# KeyBoard.net
KiCad netlist of a schematic drawn in Altium Designer
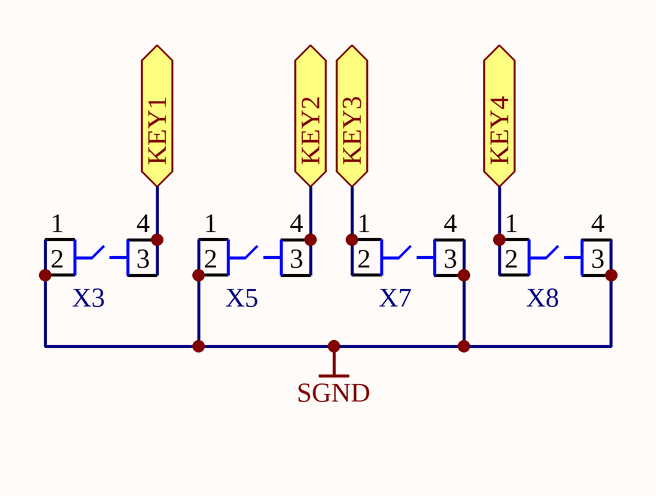
[diagram p0: KeyBoard.SchDoc]

(export (version "E")
  (design (tool "Eeschema 10.0.6"))
  (components
    (comp (ref "X3")
      (value "TACT0606")
      (footprint "TACT0606")
      (description "Tact switch 6x6mm")
      (libsource (lib "MCounter_Common") (part "TACT0606"))
    )
    (comp (ref "X5")
      (value "TACT0606")
      (footprint "TACT0606")
      (description "Tact switch 6x6mm")
      (libsource (lib "MCounter_Common") (part "TACT0606"))
    )
    (comp (ref "X7")
      (value "TACT0606")
      (footprint "TACT0606")
      (description "Tact switch 6x6mm")
      (libsource (lib "MCounter_Common") (part "TACT0606"))
    )
    (comp (ref "X8")
      (value "TACT0606")
      (footprint "TACT0606")
      (description "Tact switch 6x6mm")
      (libsource (lib "MCounter_Common") (part "TACT0606"))
    )
  )
  (nets
    (net (code "1") (name "/KEY1") (class "Default")
      (node (ref "X3") (pin "3") (pinfunction "3_3") (pintype "passive"))
      (node (ref "X3") (pin "4") (pinfunction "4_4") (pintype "passive"))
    )
    (net (code "2") (name "/KEY2") (class "Default")
      (node (ref "X5") (pin "3") (pinfunction "3_3") (pintype "passive"))
      (node (ref "X5") (pin "4") (pinfunction "4_4") (pintype "passive"))
    )
    (net (code "3") (name "/KEY3") (class "Default")
      (node (ref "X7") (pin "1") (pinfunction "1_1") (pintype "passive"))
      (node (ref "X7") (pin "2") (pinfunction "2_2") (pintype "passive"))
    )
    (net (code "4") (name "/KEY4") (class "Default")
      (node (ref "X8") (pin "1") (pinfunction "1_1") (pintype "passive"))
      (node (ref "X8") (pin "2") (pinfunction "2_2") (pintype "passive"))
    )
    (net (code "5") (name "SGND") (class "Default")
      (node (ref "X3") (pin "1") (pinfunction "1_1") (pintype "passive"))
      (node (ref "X3") (pin "2") (pinfunction "2_2") (pintype "passive"))
      (node (ref "X5") (pin "1") (pinfunction "1_1") (pintype "passive"))
      (node (ref "X5") (pin "2") (pinfunction "2_2") (pintype "passive"))
      (node (ref "X7") (pin "3") (pinfunction "3_3") (pintype "passive"))
      (node (ref "X7") (pin "4") (pinfunction "4_4") (pintype "passive"))
      (node (ref "X8") (pin "3") (pinfunction "3_3") (pintype "passive"))
      (node (ref "X8") (pin "4") (pinfunction "4_4") (pintype "passive"))
    )
  )
)
